# lab_2_somov_boost.net
KiCad netlist of a schematic drawn in Altium Designer
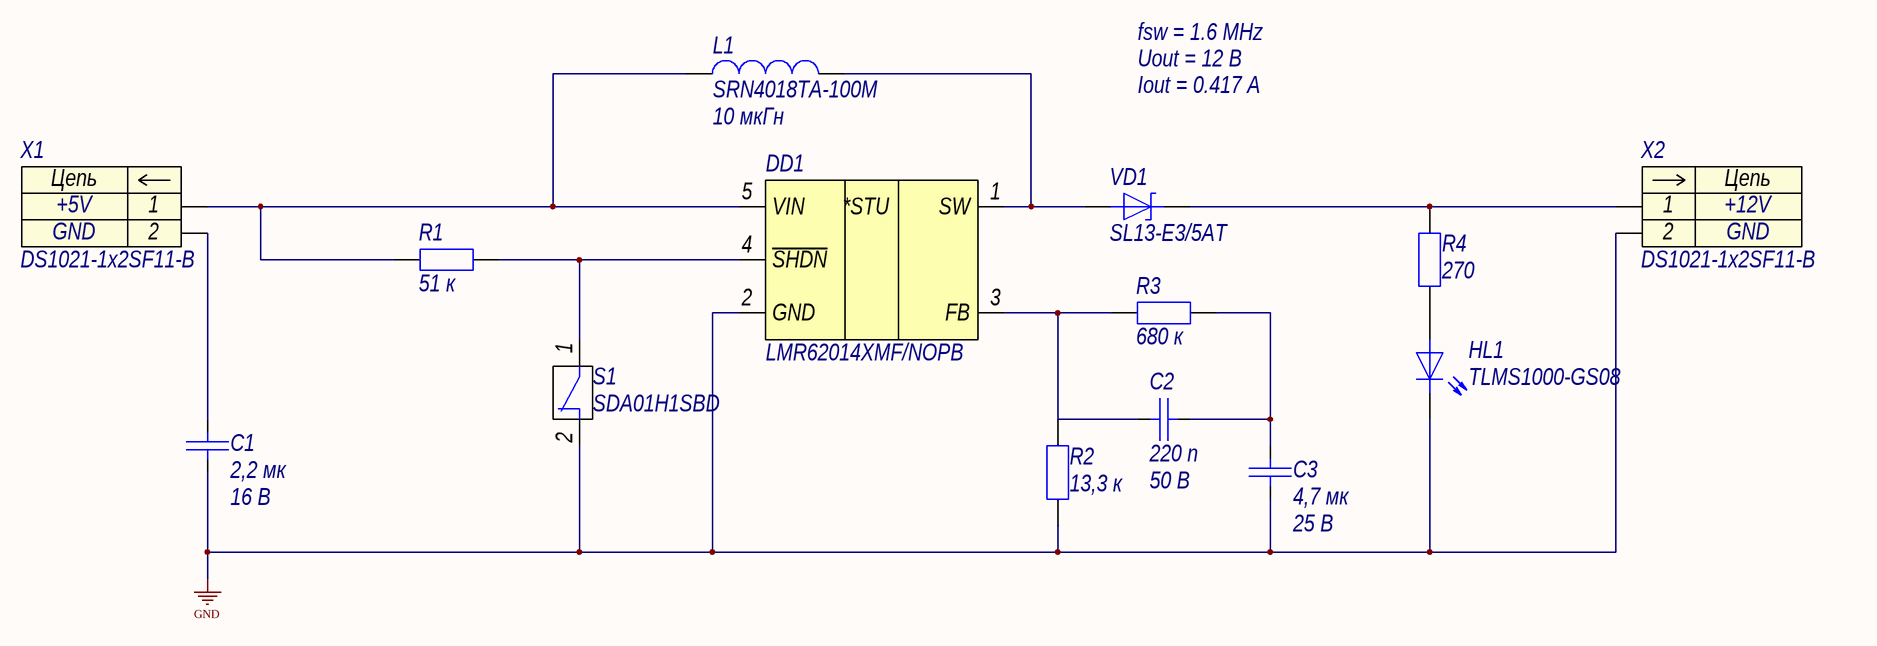
[diagram p0: lab_2_somov_boost.SchDoc]

(export (version "E")
  (design (tool "Eeschema 10.0.6"))
  (components
    (comp (ref "C1")
      (value "2,2 мк")
      (footprint "C0603")
      (description "=Описание")
      (fields (field (name "НАПРЯЖЕНИЕ") "16 В"))
      (libsource (lib "Database_Students") (part "C-NONPOLAR"))
    )
    (comp (ref "C2")
      (value "220 п")
      (footprint "C1206")
      (description "=Описание")
      (fields (field (name "НАПРЯЖЕНИЕ") "50 В"))
      (libsource (lib "Database_Students") (part "C-NONPOLAR"))
    )
    (comp (ref "C3")
      (value "4,7 мк")
      (footprint "C0603")
      (description "=Описание")
      (fields (field (name "НАПРЯЖЕНИЕ") "25 В"))
      (libsource (lib "Database_Students") (part "C-NONPOLAR"))
    )
    (comp (ref "DD1")
      (value "LMR62014XMF/NOPB")
      (footprint "SOT-23-5")
      (description "=Описание")
      (libsource (lib "Database_Students") (part "LMR64010XMF/NOPB"))
    )
    (comp (ref "HL1")
      (value "TLMS1000-GS08")
      (footprint "HL0603")
      (description "=Описание")
      (libsource (lib "Database_Students") (part "HL-COMMON"))
    )
    (comp (ref "L1")
      (value "SRN4018TA-100M")
      (footprint "SRN-2-400X400X180")
      (description "=Описание")
      (fields (field (name "ИНДУКТИВНОСТЬ") "10 мкГн"))
      (libsource (lib "Database_Students") (part "INDUCTOR-COMMON"))
    )
    (comp (ref "R1")
      (value "51 к")
      (footprint "R0603")
      (description "=Описание")
      (libsource (lib "Database_Students") (part "R-COMMON"))
    )
    (comp (ref "R2")
      (value "13,3 к")
      (footprint "R0603")
      (description "=Описание")
      (libsource (lib "Database_Students") (part "R-COMMON"))
    )
    (comp (ref "R3")
      (value "680 к")
      (footprint "R0603")
      (description "=Описание")
      (libsource (lib "Database_Students") (part "R-COMMON"))
    )
    (comp (ref "R4")
      (value "270")
      (footprint "R0603")
      (description "=Описание")
      (libsource (lib "Database_Students") (part "R-COMMON"))
    )
    (comp (ref "S1")
      (value "SDA01H1SBD")
      (footprint "SDA01H1SBD")
      (description "=Описание")
      (libsource (lib "Database_Students") (part "SWITCH-2C"))
    )
    (comp (ref "VD1")
      (value "SL13-E3/5AT")
      (footprint "DO-214AC")
      (description "=Описание")
      (libsource (lib "Database_Students") (part "DIODE-SCHOTTKY"))
    )
    (comp (ref "X1")
      (value "DS1021-1x2SF11-B")
      (footprint "DS1021-1X2SF11-B")
      (description "=Описание")
      (libsource (lib "") (part "HEADER-2-PLG_1"))
    )
    (comp (ref "X2")
      (value "DS1021-1x2SF11-B")
      (footprint "DS1021-1X2SF11-B")
      (description "=Описание")
      (libsource (lib "Database_Students") (part "HEADER-2-PLG"))
    )
  )
  (nets
    (net (code "1") (name "GND") (class "Default")
      (node (ref "C1") (pin "2") (pinfunction "2_2") (pintype "passive"))
      (node (ref "C3") (pin "1") (pinfunction "1_1") (pintype "passive"))
      (node (ref "DD1") (pin "2") (pinfunction "GND_2") (pintype "passive"))
      (node (ref "HL1") (pin "1") (pinfunction "1_1") (pintype "passive"))
      (node (ref "R2") (pin "1") (pinfunction "1_1") (pintype "passive"))
      (node (ref "S1") (pin "2") (pinfunction "2_2") (pintype "passive"))
      (node (ref "X2") (pin "2") (pinfunction "2_2") (pintype "passive"))
    )
    (net (code "2") (name "Net-(C1-Pad1)") (class "Default")
      (node (ref "C1") (pin "1") (pinfunction "1_1") (pintype "passive"))
      (node (ref "X1") (pin "2") (pinfunction "2_2") (pintype "passive"))
    )
    (net (code "3") (name "Net-(C2-Pad1)") (class "Default")
      (node (ref "C2") (pin "1") (pinfunction "1_1") (pintype "passive"))
      (node (ref "C3") (pin "2") (pinfunction "2_2") (pintype "passive"))
      (node (ref "R3") (pin "2") (pinfunction "2_2") (pintype "passive"))
    )
    (net (code "4") (name "Net-(DD1-FB)") (class "Default")
      (node (ref "C2") (pin "2") (pinfunction "2_2") (pintype "passive"))
      (node (ref "DD1") (pin "3") (pinfunction "FB_3") (pintype "passive"))
      (node (ref "R2") (pin "2") (pinfunction "2_2") (pintype "passive"))
      (node (ref "R3") (pin "1") (pinfunction "1_1") (pintype "passive"))
    )
    (net (code "5") (name "Net-(DD1-SW)") (class "Default")
      (node (ref "DD1") (pin "1") (pinfunction "SW_1") (pintype "passive"))
      (node (ref "L1") (pin "2") (pinfunction "2_2") (pintype "passive"))
      (node (ref "VD1") (pin "2") (pinfunction "2_2") (pintype "passive"))
    )
    (net (code "6") (name "Net-(DD1-VIN)") (class "Default")
      (node (ref "DD1") (pin "5") (pinfunction "VIN_5") (pintype "passive"))
      (node (ref "L1") (pin "1") (pinfunction "1_1") (pintype "passive"))
      (node (ref "R1") (pin "1") (pinfunction "1_1") (pintype "passive"))
      (node (ref "X1") (pin "1") (pinfunction "1_1") (pintype "passive"))
    )
    (net (code "7") (name "Net-(DD1-~{SHDN})") (class "Default")
      (node (ref "DD1") (pin "4") (pinfunction "~{SHDN}_4") (pintype "passive"))
      (node (ref "R1") (pin "2") (pinfunction "2_2") (pintype "passive"))
      (node (ref "S1") (pin "1") (pinfunction "1_1") (pintype "passive"))
    )
    (net (code "8") (name "Net-(HL1-Pad2)") (class "Default")
      (node (ref "HL1") (pin "2") (pinfunction "2_2") (pintype "passive"))
      (node (ref "R4") (pin "1") (pinfunction "1_1") (pintype "passive"))
    )
    (net (code "9") (name "Net-(R4-Pad2)") (class "Default")
      (node (ref "R4") (pin "2") (pinfunction "2_2") (pintype "passive"))
      (node (ref "VD1") (pin "1") (pinfunction "1_1") (pintype "passive"))
      (node (ref "X2") (pin "1") (pinfunction "1_1") (pintype "passive"))
    )
  )
)
